# TSL2561_v0_1.net
KiCad netlist of a schematic drawn in EAGLE
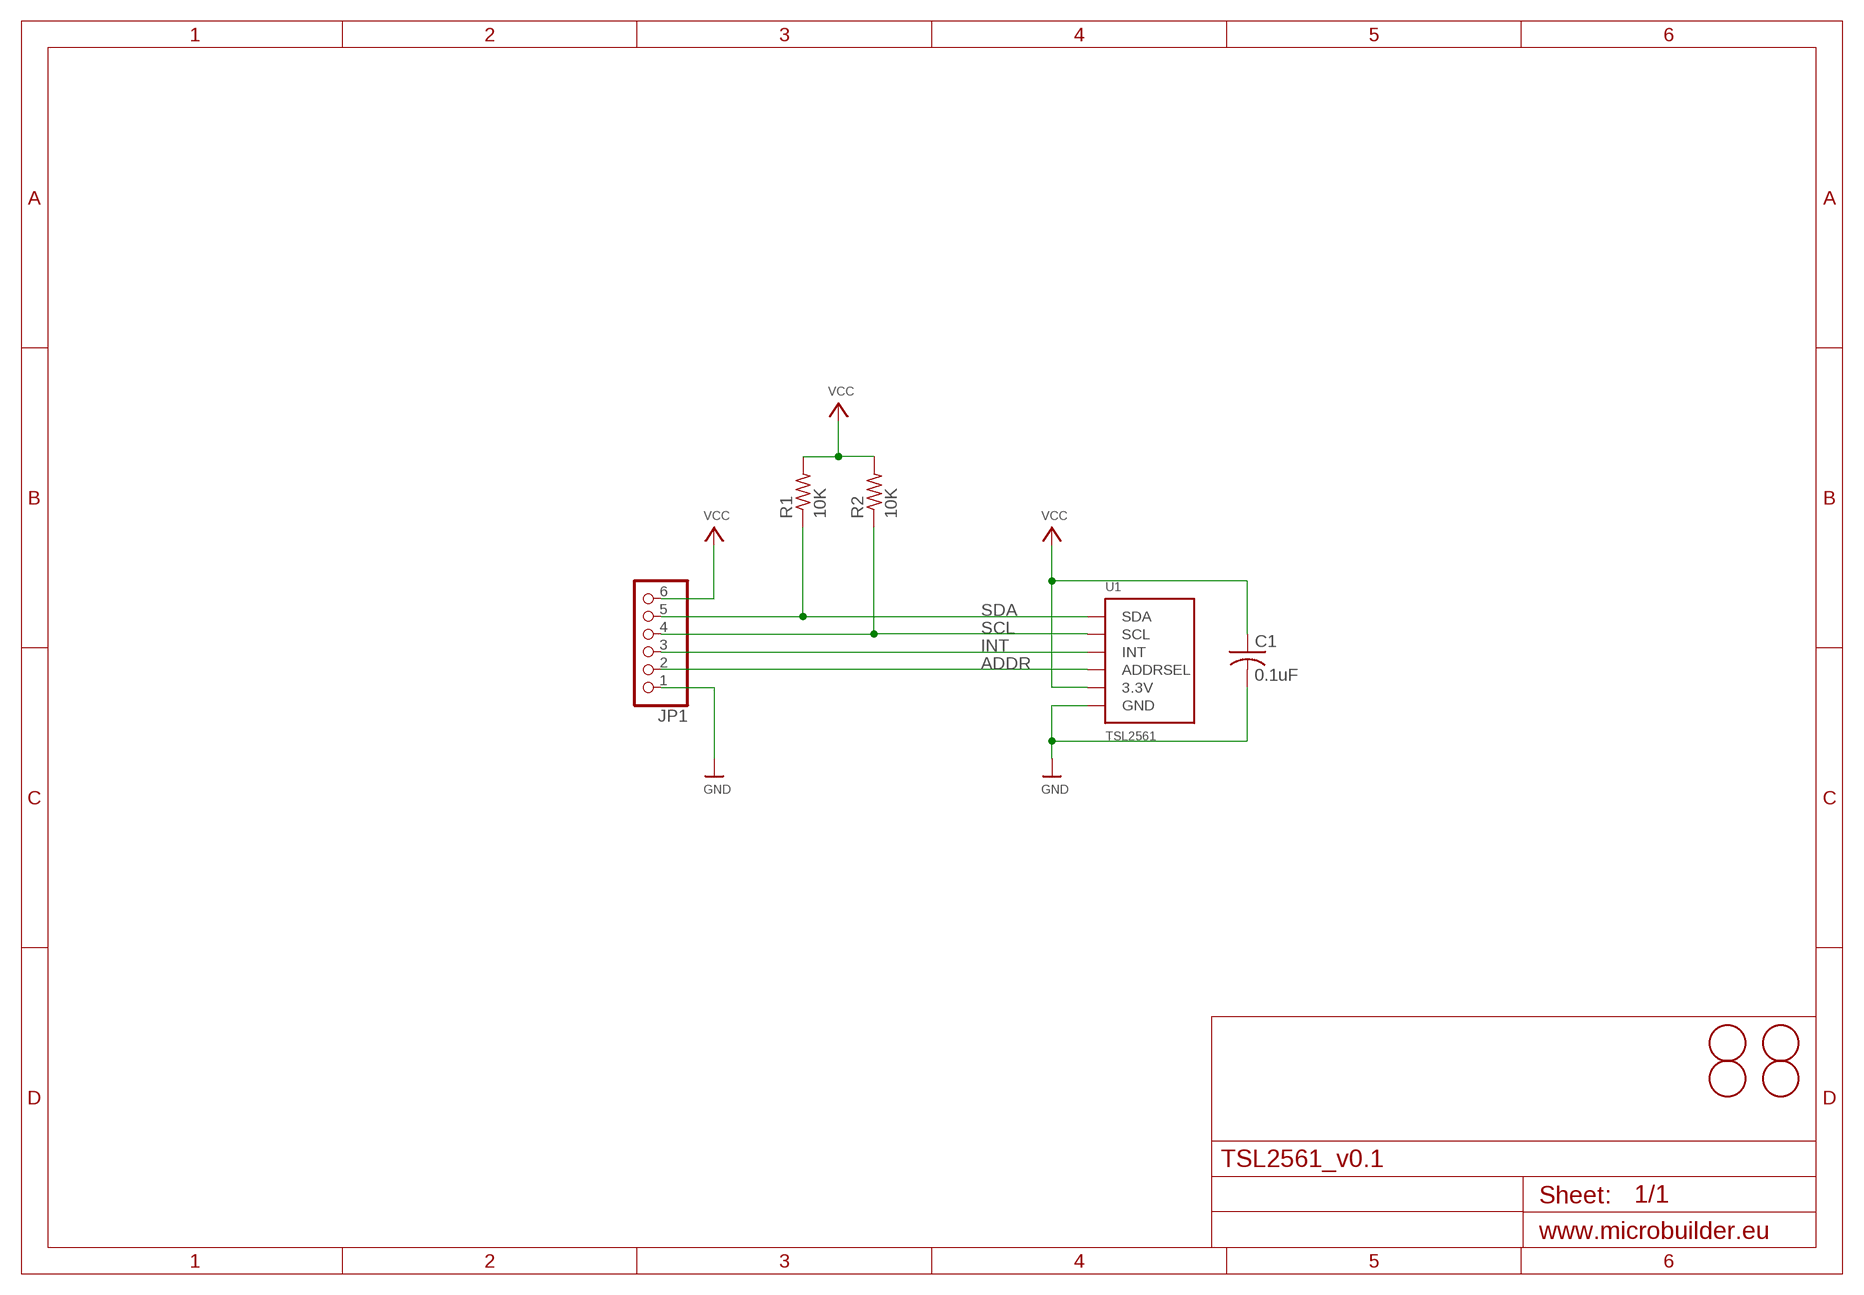
[diagram p0: schematic, sheet 1]

(export (version "E")
  (design (tool "Eeschema 10.0.6"))
  (components
    (comp (ref "C1")
      (value "0.1uF")
      (footprint "eagle-import:C0805")
      (libsource (lib "eagle-import") (part "C-USC0805"))
    )
    (comp (ref "JP1")
      (value "HEADER-1X676MIL")
      (footprint "eagle-import:1X06_ROUND_76")
      (libsource (lib "eagle-import") (part "HEADER-1X676MIL"))
    )
    (comp (ref "R1")
      (value "10K")
      (footprint "eagle-import:R0805")
      (libsource (lib "eagle-import") (part "R-US_R0805"))
    )
    (comp (ref "R2")
      (value "10K")
      (footprint "eagle-import:R0805")
      (libsource (lib "eagle-import") (part "R-US_R0805"))
    )
    (comp (ref "U$2")
      (value "FIDUCIAL")
      (footprint "eagle-import:FIDUCIAL_1MM")
      (libsource (lib "eagle-import") (part "FIDUCIAL"))
    )
    (comp (ref "U$4")
      (value "FIDUCIAL")
      (footprint "eagle-import:FIDUCIAL_1MM")
      (libsource (lib "eagle-import") (part "FIDUCIAL"))
    )
    (comp (ref "U$5")
      (value "MOUNTINGHOLE2.0")
      (footprint "eagle-import:MOUNTINGHOLE_2.0_PLATED")
      (libsource (lib "eagle-import") (part "MOUNTINGHOLE2.0"))
    )
    (comp (ref "U$6")
      (value "MOUNTINGHOLE2.0")
      (footprint "eagle-import:MOUNTINGHOLE_2.0_PLATED")
      (libsource (lib "eagle-import") (part "MOUNTINGHOLE2.0"))
    )
    (comp (ref "U1")
      (value "TSL2561")
      (footprint "eagle-import:TSL2561_FN")
      (libsource (lib "eagle-import") (part "TSL2561"))
    )
  )
  (nets
    (net (code "1") (name "/ADDR") (class "Default")
      (node (ref "JP1") (pin "2") (pinfunction "2_2") (pintype "passive"))
      (node (ref "U1") (pin "ADR") (pinfunction "ADDRSEL_ADR") (pintype "bidirectional"))
    )
    (net (code "2") (name "/INT") (class "Default")
      (node (ref "JP1") (pin "3") (pinfunction "3_3") (pintype "passive"))
      (node (ref "U1") (pin "INT") (pinfunction "INT_INT") (pintype "bidirectional"))
    )
    (net (code "3") (name "/SCL") (class "Default")
      (node (ref "JP1") (pin "4") (pinfunction "4_4") (pintype "passive"))
      (node (ref "R2") (pin "1") (pinfunction "1_1") (pintype "passive"))
      (node (ref "U1") (pin "CLK") (pinfunction "SCL_CLK") (pintype "bidirectional"))
    )
    (net (code "4") (name "/SDA") (class "Default")
      (node (ref "JP1") (pin "5") (pinfunction "5_5") (pintype "passive"))
      (node (ref "R1") (pin "1") (pinfunction "1_1") (pintype "passive"))
      (node (ref "U1") (pin "DATA") (pinfunction "SDA_DATA") (pintype "bidirectional"))
    )
    (net (code "5") (name "GND") (class "Default")
      (node (ref "C1") (pin "2") (pinfunction "2_2") (pintype "passive"))
      (node (ref "JP1") (pin "1") (pinfunction "1_1") (pintype "passive"))
      (node (ref "U1") (pin "VSS") (pinfunction "GND_VSS") (pintype "bidirectional"))
    )
    (net (code "6") (name "VCC") (class "Default")
      (node (ref "C1") (pin "1") (pinfunction "1_1") (pintype "passive"))
      (node (ref "JP1") (pin "6") (pinfunction "6_6") (pintype "passive"))
      (node (ref "R1") (pin "2") (pinfunction "2_2") (pintype "passive"))
      (node (ref "R2") (pin "2") (pinfunction "2_2") (pintype "passive"))
      (node (ref "U1") (pin "VDD") (pinfunction "3.3V_VDD") (pintype "bidirectional"))
    )
  )
)
